# Protocell_module.net
KiCad netlist of a schematic drawn in EAGLE
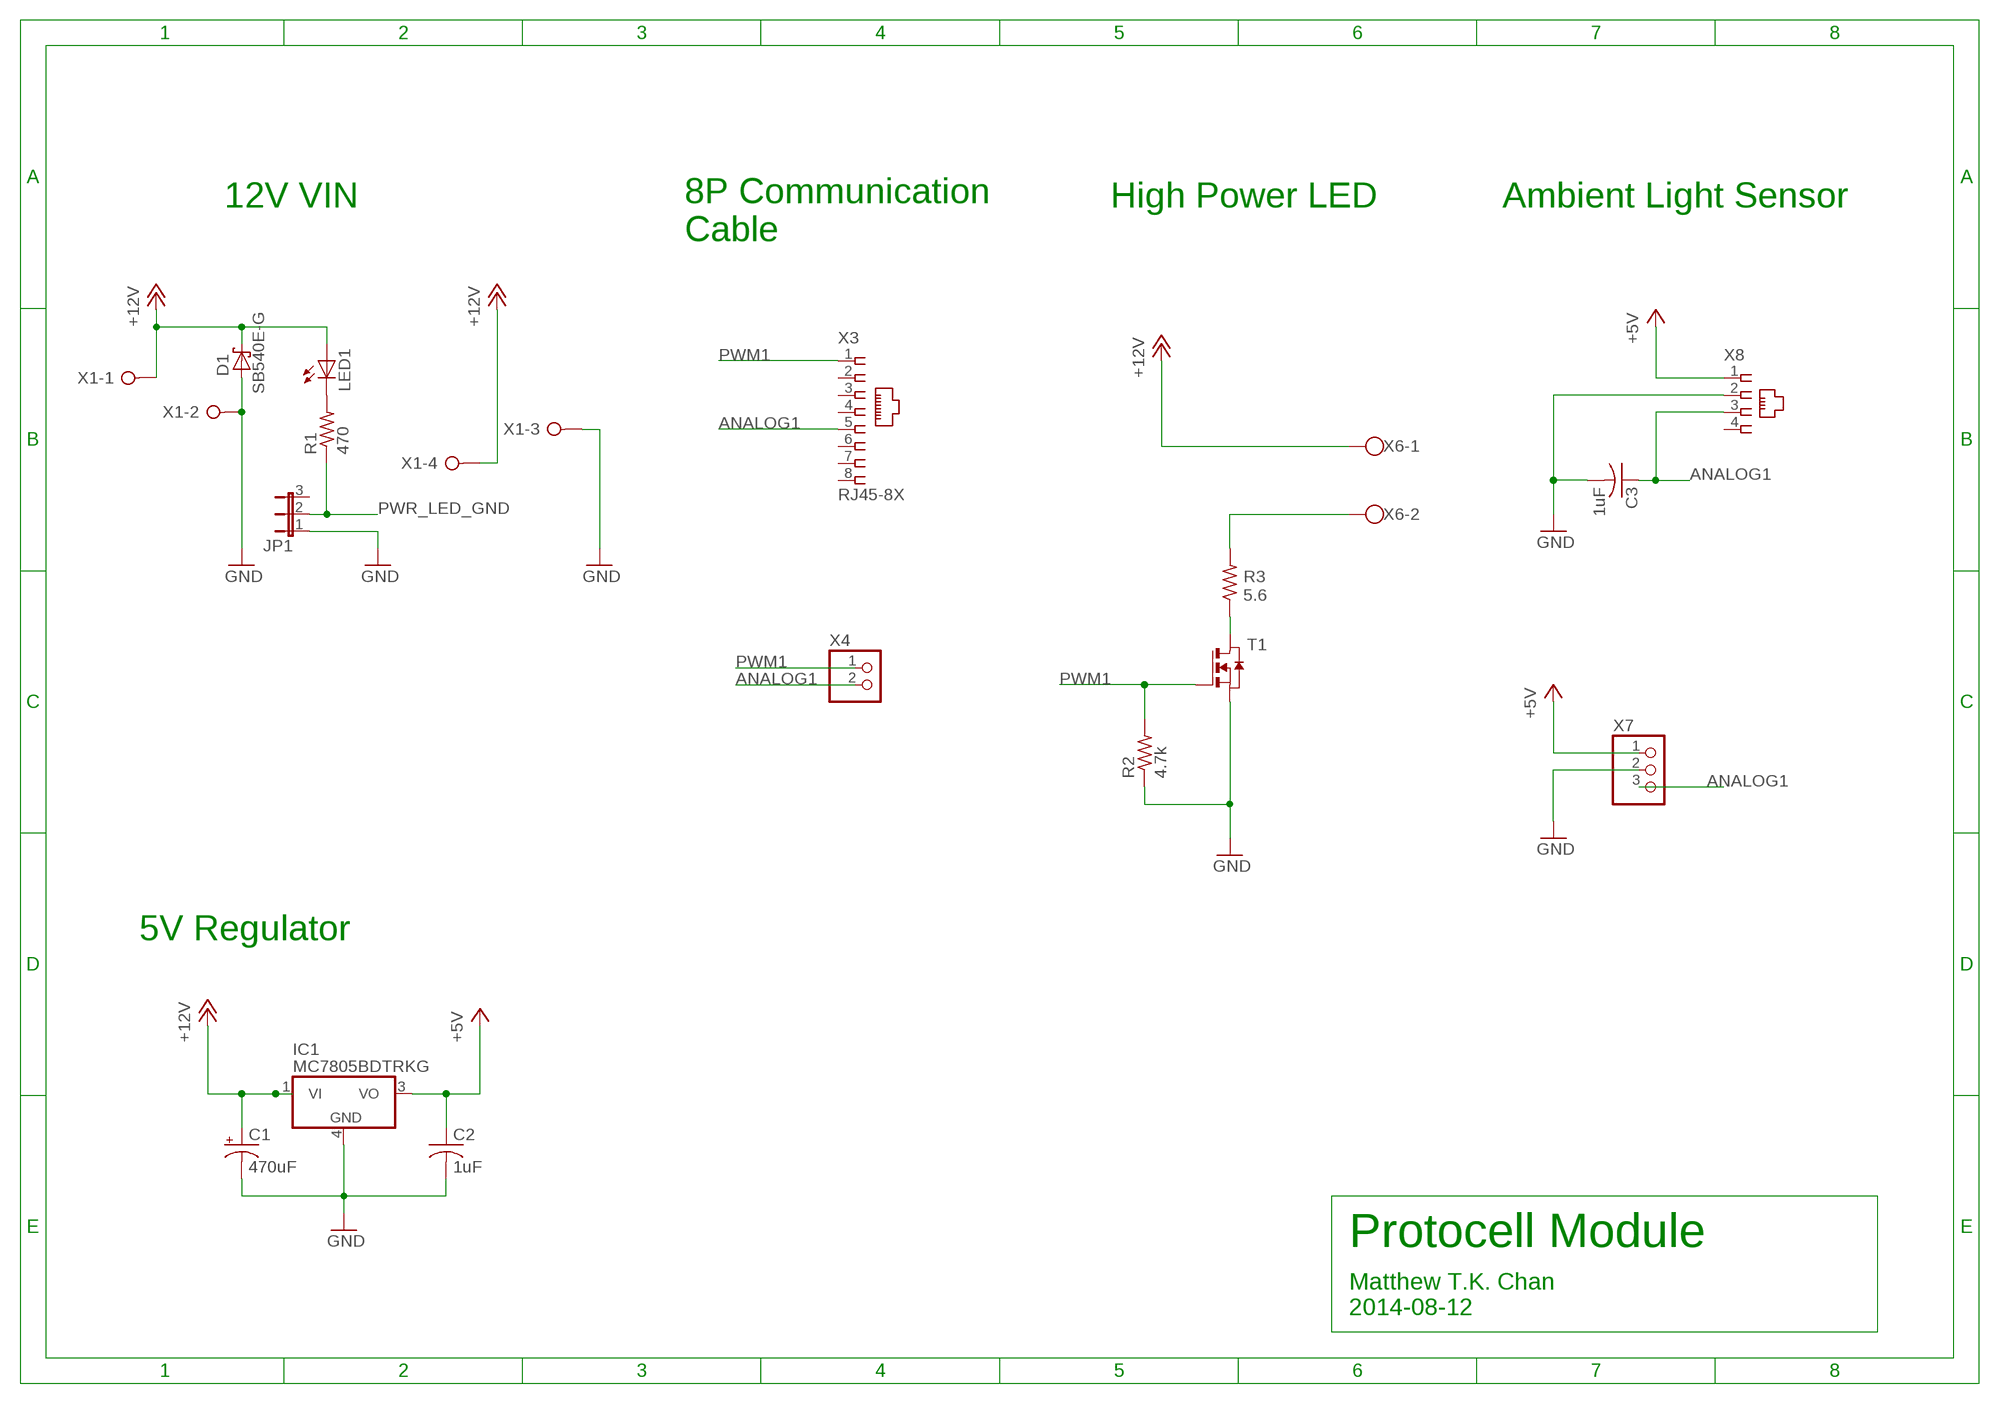
[diagram p0: schematic, sheet 1]

(export (version "E")
  (design (tool "Eeschema 10.0.6"))
  (components
    (comp (ref "C1")
      (value "470uF")
      (footprint "eagle-import:E5-10,5")
      (libsource (lib "eagle-import") (part "CPOL-USE5-10.5"))
    )
    (comp (ref "C2")
      (value "1uF")
      (footprint "eagle-import:C0603")
      (libsource (lib "eagle-import") (part "C-USC0603"))
    )
    (comp (ref "C3")
      (value "1uF")
      (footprint "eagle-import:C0603")
      (libsource (lib "eagle-import") (part "C-USC0603"))
    )
    (comp (ref "D1")
      (value "SB540E-G")
      (footprint "eagle-import:DO201T15")
      (libsource (lib "eagle-import") (part "SB540E-G"))
    )
    (comp (ref "IC1")
      (value "MC7805BDTRKG")
      (footprint "eagle-import:DPACK_3")
      (libsource (lib "eagle-import") (part "MC7805BDTRKG"))
    )
    (comp (ref "JP1")
      (value "JP2E")
      (footprint "eagle-import:JP2")
      (libsource (lib "eagle-import") (part "JP2E"))
    )
    (comp (ref "LED1")
      (value "LEDSML1206")
      (footprint "eagle-import:SML1206")
      (libsource (lib "eagle-import") (part "LEDSML1206"))
    )
    (comp (ref "R1")
      (value "470")
      (footprint "eagle-import:R0603")
      (libsource (lib "eagle-import") (part "R-US_R0603"))
    )
    (comp (ref "R2")
      (value "4.7k")
      (footprint "eagle-import:R0603")
      (libsource (lib "eagle-import") (part "R-US_R0603"))
    )
    (comp (ref "R3")
      (value "5.6")
      (footprint "eagle-import:YAGEO_SQP500JB")
      (libsource (lib "eagle-import") (part "SQP500JB-5R6"))
    )
    (comp (ref "T1")
      (value "NTD5867NLT4G")
      (footprint "eagle-import:DPACK")
      (libsource (lib "eagle-import") (part "NTD5867NLT4G"))
    )
    (comp (ref "X1")
      (value "W237-04P")
      (footprint "eagle-import:W237-4P")
      (libsource (lib "eagle-import") (part "W237-04P"))
    )
    (comp (ref "X3")
      (value "RJ45-8X")
      (footprint "eagle-import:RJ45-NO-SHIELD")
      (libsource (lib "eagle-import") (part "RJ45-8X"))
    )
    (comp (ref "X4")
      (value "PINHD-1X2")
      (footprint "eagle-import:1X02")
      (libsource (lib "eagle-import") (part "PINHD-1X2"))
    )
    (comp (ref "X6")
      (value "W237-102")
      (footprint "eagle-import:W237-102")
      (fields (field (name "MPN") "237-102"))
      (libsource (lib "eagle-import") (part "W237-102"))
    )
    (comp (ref "X7")
      (value "PINHD-1X3")
      (footprint "eagle-import:1X03")
      (libsource (lib "eagle-import") (part "PINHD-1X3"))
    )
    (comp (ref "X8")
      (value "558872-1")
      (footprint "eagle-import:558872-1")
      (fields (field (name "MF") "TYCO ELECTRONICS") (field (name "MPN") "5558872-1"))
      (libsource (lib "eagle-import") (part "558872-1"))
    )
  )
  (nets
    (net (code "1") (name "+5V") (class "Default")
      (node (ref "C2") (pin "1") (pinfunction "1_1") (pintype "passive"))
      (node (ref "IC1") (pin "3") (pinfunction "VO_3") (pintype "passive"))
      (node (ref "X7") (pin "1") (pinfunction "1_1") (pintype "passive"))
      (node (ref "X8") (pin "1") (pinfunction "1_1") (pintype "passive"))
    )
    (net (code "2") (name "+12V") (class "Default")
      (node (ref "C1") (pin "+") (pinfunction "+_+") (pintype "passive"))
      (node (ref "D1") (pin "C") (pinfunction "C_C") (pintype "passive"))
      (node (ref "IC1") (pin "1") (pinfunction "VI_1") (pintype "input"))
      (node (ref "LED1") (pin "A") (pinfunction "A_A") (pintype "passive"))
      (node (ref "X1") (pin "1") (pinfunction "KL_1") (pintype "passive"))
      (node (ref "X1") (pin "4") (pinfunction "KL_4") (pintype "passive"))
      (node (ref "X6") (pin "1") (pinfunction "KL_1") (pintype "passive"))
    )
    (net (code "3") (name "/ANALOG1") (class "Default")
      (node (ref "C3") (pin "1") (pinfunction "1_1") (pintype "passive"))
      (node (ref "X3") (pin "5") (pinfunction "5_5") (pintype "passive"))
      (node (ref "X4") (pin "2") (pinfunction "2_2") (pintype "passive"))
      (node (ref "X7") (pin "3") (pinfunction "3_3") (pintype "passive"))
      (node (ref "X8") (pin "3") (pinfunction "3_3") (pintype "passive"))
    )
    (net (code "4") (name "/PWM1") (class "Default")
      (node (ref "R2") (pin "2") (pinfunction "2_2") (pintype "passive"))
      (node (ref "T1") (pin "1") (pinfunction "G_1") (pintype "passive"))
      (node (ref "X3") (pin "1") (pinfunction "1_1") (pintype "passive"))
      (node (ref "X4") (pin "1") (pinfunction "1_1") (pintype "passive"))
    )
    (net (code "5") (name "/PWR_LED_GND") (class "Default")
      (node (ref "JP1") (pin "2") (pinfunction "2_2") (pintype "passive"))
      (node (ref "R1") (pin "1") (pinfunction "1_1") (pintype "passive"))
    )
    (net (code "6") (name "GND") (class "Default")
      (node (ref "C1") (pin "-") (pinfunction "-_-") (pintype "passive"))
      (node (ref "C2") (pin "2") (pinfunction "2_2") (pintype "passive"))
      (node (ref "C3") (pin "2") (pinfunction "2_2") (pintype "passive"))
      (node (ref "D1") (pin "A") (pinfunction "A_A") (pintype "passive"))
      (node (ref "IC1") (pin "4") (pinfunction "GND_4") (pintype "passive"))
      (node (ref "JP1") (pin "1") (pinfunction "1_1") (pintype "passive"))
      (node (ref "R2") (pin "1") (pinfunction "1_1") (pintype "passive"))
      (node (ref "T1") (pin "3") (pinfunction "S_3") (pintype "passive"))
      (node (ref "X1") (pin "2") (pinfunction "KL_2") (pintype "passive"))
      (node (ref "X1") (pin "3") (pinfunction "KL_3") (pintype "passive"))
      (node (ref "X7") (pin "2") (pinfunction "2_2") (pintype "passive"))
      (node (ref "X8") (pin "2") (pinfunction "2_2") (pintype "passive"))
    )
    (net (code "7") (name "Net-(LED1-PadC)") (class "Default")
      (node (ref "LED1") (pin "C") (pinfunction "C_C") (pintype "passive"))
      (node (ref "R1") (pin "2") (pinfunction "2_2") (pintype "passive"))
    )
    (net (code "8") (name "Net-(T1-D)") (class "Default")
      (node (ref "R3") (pin "1") (pinfunction "1_1") (pintype "passive"))
      (node (ref "T1") (pin "2") (pinfunction "D_2") (pintype "passive"))
    )
    (net (code "9") (name "Net-(X6B-KL)") (class "Default")
      (node (ref "R3") (pin "2") (pinfunction "2_2") (pintype "passive"))
      (node (ref "X6") (pin "2") (pinfunction "KL_2") (pintype "passive"))
    )
    (net (code "10") (name "unconnected-(JP1-Pad3)") (class "Default")
      (node (ref "JP1") (pin "3") (pinfunction "3_3") (pintype "passive"))
    )
    (net (code "11") (name "unconnected-(X3-Pad2)") (class "Default")
      (node (ref "X3") (pin "2") (pinfunction "2_2") (pintype "passive"))
    )
    (net (code "12") (name "unconnected-(X3-Pad3)") (class "Default")
      (node (ref "X3") (pin "3") (pinfunction "3_3") (pintype "passive"))
    )
    (net (code "13") (name "unconnected-(X3-Pad4)") (class "Default")
      (node (ref "X3") (pin "4") (pinfunction "4_4") (pintype "passive"))
    )
    (net (code "14") (name "unconnected-(X3-Pad6)") (class "Default")
      (node (ref "X3") (pin "6") (pinfunction "6_6") (pintype "passive"))
    )
    (net (code "15") (name "unconnected-(X3-Pad7)") (class "Default")
      (node (ref "X3") (pin "7") (pinfunction "7_7") (pintype "passive"))
    )
    (net (code "16") (name "unconnected-(X3-Pad8)") (class "Default")
      (node (ref "X3") (pin "8") (pinfunction "8_8") (pintype "passive"))
    )
    (net (code "17") (name "unconnected-(X8-Pad4)") (class "Default")
      (node (ref "X8") (pin "4") (pinfunction "4_4") (pintype "passive"))
    )
  )
)
